# usb-board.net
KiCad netlist of a schematic drawn in EAGLE
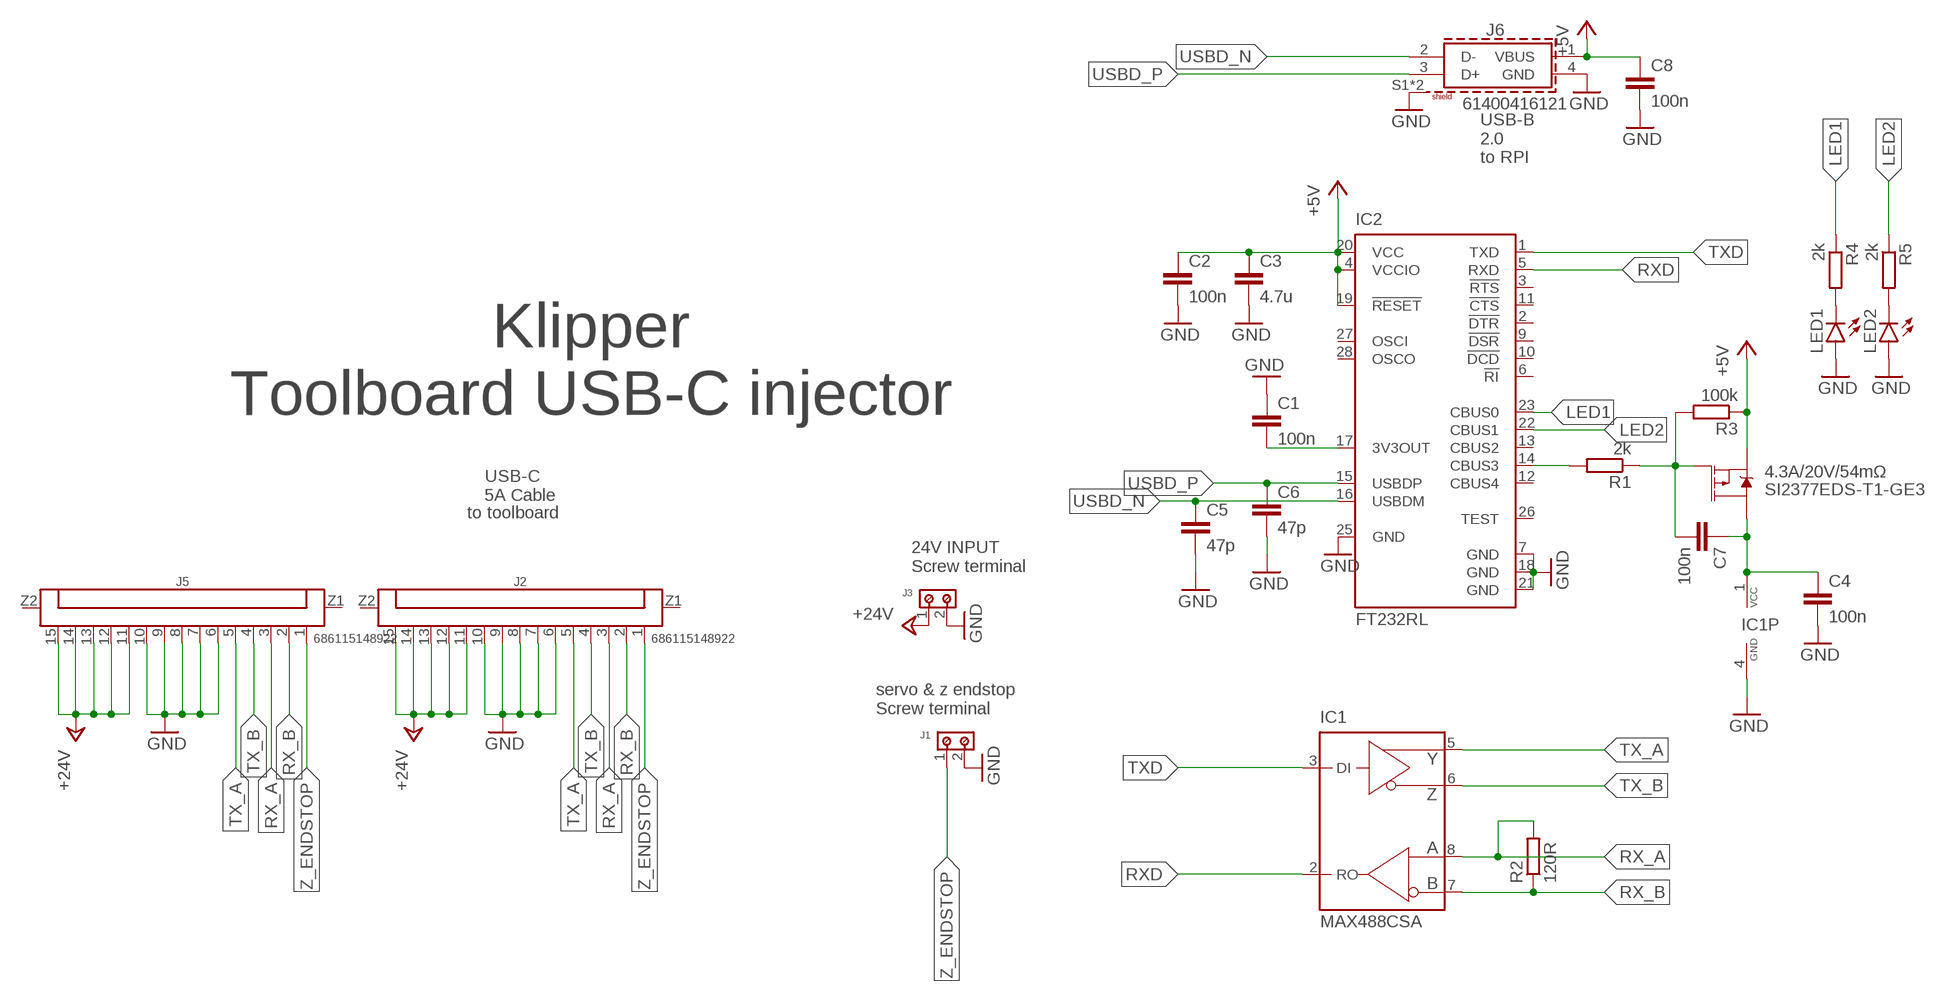
[diagram p0: schematic, sheet 1]

(export (version "E")
  (design (tool "Eeschema 10.0.6"))
  (components
    (comp (ref "C1")
      (value "100n")
      (footprint "eagle-import:C0805")
      (libsource (lib "eagle-import") (part "C-EUC0805"))
    )
    (comp (ref "C2")
      (value "100n")
      (footprint "eagle-import:C0805")
      (libsource (lib "eagle-import") (part "C-EUC0805"))
    )
    (comp (ref "C3")
      (value "4.7u")
      (footprint "eagle-import:C0805")
      (libsource (lib "eagle-import") (part "C-EUC0805"))
    )
    (comp (ref "C4")
      (value "100n")
      (footprint "eagle-import:C0805")
      (libsource (lib "eagle-import") (part "C-EUC0805"))
    )
    (comp (ref "C5")
      (value "47p")
      (footprint "eagle-import:C0805")
      (libsource (lib "eagle-import") (part "C-EUC0805"))
    )
    (comp (ref "C6")
      (value "47p")
      (footprint "eagle-import:C0805")
      (libsource (lib "eagle-import") (part "C-EUC0805"))
    )
    (comp (ref "C7")
      (value "100n")
      (footprint "eagle-import:C0805")
      (libsource (lib "eagle-import") (part "C-EUC0805"))
    )
    (comp (ref "C8")
      (value "100n")
      (footprint "eagle-import:C0805")
      (libsource (lib "eagle-import") (part "C-EUC0805"))
    )
    (comp (ref "IC1")
      (value "MAX488CSA")
      (footprint "eagle-import:SO08")
      (fields (field (name "MF") "MAXIM"))
      (libsource (lib "eagle-import") (part "MAX488CSA"))
    )
    (comp (ref "IC2")
      (value "FT232RL")
      (footprint "eagle-import:SSOP28")
      (libsource (lib "eagle-import") (part "FT232RL"))
    )
    (comp (ref "J1")
      (value "691103110002")
      (footprint "eagle-import:691103110002")
      (libsource (lib "eagle-import") (part "691103110002"))
    )
    (comp (ref "J2")
      (value "686115148922")
      (footprint "eagle-import:686115148922")
      (libsource (lib "eagle-import") (part "6861XX148922_686115148922"))
    )
    (comp (ref "J3")
      (value "691103110002")
      (footprint "eagle-import:691103110002")
      (libsource (lib "eagle-import") (part "691103110002"))
    )
    (comp (ref "J5")
      (value "686115148922")
      (footprint "eagle-import:686115148922")
      (libsource (lib "eagle-import") (part "6861XX148922_686115148922"))
    )
    (comp (ref "J6")
      (value "61400416121")
      (footprint "eagle-import:61400416121")
      (libsource (lib "eagle-import") (part "61400416121"))
    )
    (comp (ref "LED1")
      (value "LEDCHIPLED_0805")
      (footprint "eagle-import:CHIPLED_0805")
      (libsource (lib "eagle-import") (part "LEDCHIPLED_0805"))
    )
    (comp (ref "LED2")
      (value "LEDCHIPLED_0805")
      (footprint "eagle-import:CHIPLED_0805")
      (libsource (lib "eagle-import") (part "LEDCHIPLED_0805"))
    )
    (comp (ref "R1")
      (value "2k")
      (footprint "eagle-import:R0805")
      (libsource (lib "eagle-import") (part "R-EU_R0805"))
    )
    (comp (ref "R2")
      (value "120R")
      (footprint "eagle-import:R0805")
      (libsource (lib "eagle-import") (part "R-EU_R0805"))
    )
    (comp (ref "R3")
      (value "100k")
      (footprint "eagle-import:R0805")
      (libsource (lib "eagle-import") (part "R-EU_R0805"))
    )
    (comp (ref "R4")
      (value "2k")
      (footprint "eagle-import:R0805")
      (libsource (lib "eagle-import") (part "R-EU_R0805"))
    )
    (comp (ref "R5")
      (value "2k")
      (footprint "eagle-import:R0805")
      (libsource (lib "eagle-import") (part "R-EU_R0805"))
    )
    (comp (ref "SI2377EDS-T1-GE3")
      (value "4.3A/20V/54mΩ")
      (footprint "eagle-import:SOT23-3")
      (libsource (lib "eagle-import") (part "MOSFET_PCH-IRLML2244"))
    )
  )
  (nets
    (net (code "1") (name "+5V") (class "Default")
      (node (ref "C2") (pin "1") (pinfunction "1_1") (pintype "passive"))
      (node (ref "C3") (pin "1") (pinfunction "1_1") (pintype "passive"))
      (node (ref "C8") (pin "1") (pinfunction "1_1") (pintype "passive"))
      (node (ref "IC2") (pin "19") (pinfunction "~{RESET}_19") (pintype "input"))
      (node (ref "IC2") (pin "20") (pinfunction "VCC_20") (pintype "power_in"))
      (node (ref "IC2") (pin "4") (pinfunction "VCCIO_4") (pintype "power_in"))
      (node (ref "J6") (pin "1") (pinfunction "VBUS_1") (pintype "passive"))
      (node (ref "R3") (pin "1") (pinfunction "1_1") (pintype "passive"))
      (node (ref "SI2377EDS-T1-GE3") (pin "2") (pinfunction "S_2") (pintype "bidirectional"))
    )
    (net (code "2") (name "+24V") (class "Default")
      (node (ref "J2") (pin "11") (pinfunction "11_11") (pintype "passive"))
      (node (ref "J2") (pin "12") (pinfunction "12_12") (pintype "passive"))
      (node (ref "J2") (pin "13") (pinfunction "13_13") (pintype "passive"))
      (node (ref "J2") (pin "14") (pinfunction "14_14") (pintype "passive"))
      (node (ref "J2") (pin "15") (pinfunction "15_15") (pintype "passive"))
      (node (ref "J3") (pin "1") (pinfunction "1_1") (pintype "passive"))
      (node (ref "J5") (pin "11") (pinfunction "11_11") (pintype "passive"))
      (node (ref "J5") (pin "12") (pinfunction "12_12") (pintype "passive"))
      (node (ref "J5") (pin "13") (pinfunction "13_13") (pintype "passive"))
      (node (ref "J5") (pin "14") (pinfunction "14_14") (pintype "passive"))
      (node (ref "J5") (pin "15") (pinfunction "15_15") (pintype "passive"))
    )
    (net (code "3") (name "GND") (class "Default")
      (node (ref "C1") (pin "1") (pinfunction "1_1") (pintype "passive"))
      (node (ref "C2") (pin "2") (pinfunction "2_2") (pintype "passive"))
      (node (ref "C3") (pin "2") (pinfunction "2_2") (pintype "passive"))
      (node (ref "C4") (pin "2") (pinfunction "2_2") (pintype "passive"))
      (node (ref "C5") (pin "2") (pinfunction "2_2") (pintype "passive"))
      (node (ref "C6") (pin "2") (pinfunction "2_2") (pintype "passive"))
      (node (ref "C8") (pin "2") (pinfunction "2_2") (pintype "passive"))
      (node (ref "IC1") (pin "4") (pinfunction "GND_4") (pintype "power_in"))
      (node (ref "IC2") (pin "18") (pinfunction "GND_18") (pintype "power_in"))
      (node (ref "IC2") (pin "21") (pinfunction "GND_21") (pintype "power_in"))
      (node (ref "IC2") (pin "25") (pinfunction "GND_25") (pintype "power_in"))
      (node (ref "IC2") (pin "7") (pinfunction "GND_7") (pintype "power_in"))
      (node (ref "J1") (pin "2") (pinfunction "2_2") (pintype "passive"))
      (node (ref "J2") (pin "10") (pinfunction "10_10") (pintype "passive"))
      (node (ref "J2") (pin "6") (pinfunction "6_6") (pintype "passive"))
      (node (ref "J2") (pin "7") (pinfunction "7_7") (pintype "passive"))
      (node (ref "J2") (pin "8") (pinfunction "8_8") (pintype "passive"))
      (node (ref "J2") (pin "9") (pinfunction "9_9") (pintype "passive"))
      (node (ref "J3") (pin "2") (pinfunction "2_2") (pintype "passive"))
      (node (ref "J5") (pin "10") (pinfunction "10_10") (pintype "passive"))
      (node (ref "J5") (pin "6") (pinfunction "6_6") (pintype "passive"))
      (node (ref "J5") (pin "7") (pinfunction "7_7") (pintype "passive"))
      (node (ref "J5") (pin "8") (pinfunction "8_8") (pintype "passive"))
      (node (ref "J5") (pin "9") (pinfunction "9_9") (pintype "passive"))
      (node (ref "J6") (pin "4") (pinfunction "GND_4") (pintype "passive"))
      (node (ref "J6") (pin "S1") (pinfunction "SHIELD_S1") (pintype "passive"))
      (node (ref "J6") (pin "S2") (pinfunction "SHIELD_S2") (pintype "passive"))
      (node (ref "LED1") (pin "A") (pinfunction "A_A") (pintype "passive"))
      (node (ref "LED2") (pin "A") (pinfunction "A_A") (pintype "passive"))
    )
    (net (code "4") (name "LED1") (class "Default")
      (node (ref "IC2") (pin "23") (pinfunction "CBUS0_23") (pintype "bidirectional"))
      (node (ref "R4") (pin "1") (pinfunction "1_1") (pintype "passive"))
    )
    (net (code "5") (name "LED2") (class "Default")
      (node (ref "IC2") (pin "22") (pinfunction "CBUS1_22") (pintype "bidirectional"))
      (node (ref "R5") (pin "1") (pinfunction "1_1") (pintype "passive"))
    )
    (net (code "6") (name "Net-(IC1B-VCC)") (class "Default")
      (node (ref "C4") (pin "1") (pinfunction "1_1") (pintype "passive"))
      (node (ref "C7") (pin "1") (pinfunction "1_1") (pintype "passive"))
      (node (ref "IC1") (pin "1") (pinfunction "VCC_1") (pintype "power_in"))
      (node (ref "SI2377EDS-T1-GE3") (pin "3") (pinfunction "D_3") (pintype "bidirectional"))
    )
    (net (code "7") (name "Net-(IC2-3V3OUT)") (class "Default")
      (node (ref "C1") (pin "2") (pinfunction "2_2") (pintype "passive"))
      (node (ref "IC2") (pin "17") (pinfunction "3V3OUT_17") (pintype "output"))
    )
    (net (code "8") (name "Net-(IC2-CBUS3)") (class "Default")
      (node (ref "IC2") (pin "14") (pinfunction "CBUS3_14") (pintype "bidirectional"))
      (node (ref "R1") (pin "2") (pinfunction "2_2") (pintype "passive"))
    )
    (net (code "9") (name "Net-(LED1-PadC)") (class "Default")
      (node (ref "LED1") (pin "C") (pinfunction "C_C") (pintype "passive"))
      (node (ref "R4") (pin "2") (pinfunction "2_2") (pintype "passive"))
    )
    (net (code "10") (name "Net-(LED2-PadC)") (class "Default")
      (node (ref "LED2") (pin "C") (pinfunction "C_C") (pintype "passive"))
      (node (ref "R5") (pin "2") (pinfunction "2_2") (pintype "passive"))
    )
    (net (code "11") (name "Net-(SI2377EDS-T1-GE3-G)") (class "Default")
      (node (ref "C7") (pin "2") (pinfunction "2_2") (pintype "passive"))
      (node (ref "R1") (pin "1") (pinfunction "1_1") (pintype "passive"))
      (node (ref "R3") (pin "2") (pinfunction "2_2") (pintype "passive"))
      (node (ref "SI2377EDS-T1-GE3") (pin "1") (pinfunction "G_1") (pintype "bidirectional"))
    )
    (net (code "12") (name "RXD") (class "Default")
      (node (ref "IC1") (pin "2") (pinfunction "RO_2") (pintype "output"))
      (node (ref "IC2") (pin "5") (pinfunction "RXD_5") (pintype "input"))
    )
    (net (code "13") (name "RX_A") (class "Default")
      (node (ref "IC1") (pin "8") (pinfunction "A_8") (pintype "input"))
      (node (ref "J2") (pin "3") (pinfunction "3_3") (pintype "passive"))
      (node (ref "J5") (pin "3") (pinfunction "3_3") (pintype "passive"))
      (node (ref "R2") (pin "2") (pinfunction "2_2") (pintype "passive"))
    )
    (net (code "14") (name "RX_B") (class "Default")
      (node (ref "IC1") (pin "7") (pinfunction "B_7") (pintype "input"))
      (node (ref "J2") (pin "2") (pinfunction "2_2") (pintype "passive"))
      (node (ref "J5") (pin "2") (pinfunction "2_2") (pintype "passive"))
      (node (ref "R2") (pin "1") (pinfunction "1_1") (pintype "passive"))
    )
    (net (code "15") (name "TXD") (class "Default")
      (node (ref "IC1") (pin "3") (pinfunction "DI_3") (pintype "input"))
      (node (ref "IC2") (pin "1") (pinfunction "TXD_1") (pintype "output"))
    )
    (net (code "16") (name "TX_A") (class "Default")
      (node (ref "IC1") (pin "5") (pinfunction "Y_5") (pintype "output"))
      (node (ref "J2") (pin "5") (pinfunction "5_5") (pintype "passive"))
      (node (ref "J5") (pin "5") (pinfunction "5_5") (pintype "passive"))
    )
    (net (code "17") (name "TX_B") (class "Default")
      (node (ref "IC1") (pin "6") (pinfunction "Z_6") (pintype "output"))
      (node (ref "J2") (pin "4") (pinfunction "4_4") (pintype "passive"))
      (node (ref "J5") (pin "4") (pinfunction "4_4") (pintype "passive"))
    )
    (net (code "18") (name "USBD_N") (class "Default")
      (node (ref "C5") (pin "1") (pinfunction "1_1") (pintype "passive"))
      (node (ref "IC2") (pin "16") (pinfunction "USBDM_16") (pintype "bidirectional"))
      (node (ref "J6") (pin "2") (pinfunction "D-_2") (pintype "passive"))
    )
    (net (code "19") (name "USBD_P") (class "Default")
      (node (ref "C6") (pin "1") (pinfunction "1_1") (pintype "passive"))
      (node (ref "IC2") (pin "15") (pinfunction "USBDP_15") (pintype "bidirectional"))
      (node (ref "J6") (pin "3") (pinfunction "D+_3") (pintype "passive"))
    )
    (net (code "20") (name "Z_ENDSTOP") (class "Default")
      (node (ref "J1") (pin "1") (pinfunction "1_1") (pintype "passive"))
      (node (ref "J2") (pin "1") (pinfunction "1_1") (pintype "passive"))
      (node (ref "J5") (pin "1") (pinfunction "1_1") (pintype "passive"))
    )
    (net (code "21") (name "unconnected-(IC2-CBUS2-Pad13)") (class "Default")
      (node (ref "IC2") (pin "13") (pinfunction "CBUS2_13") (pintype "bidirectional"))
    )
    (net (code "22") (name "unconnected-(IC2-CBUS4-Pad12)") (class "Default")
      (node (ref "IC2") (pin "12") (pinfunction "CBUS4_12") (pintype "bidirectional"))
    )
    (net (code "23") (name "unconnected-(IC2-OSCI-Pad27)") (class "Default")
      (node (ref "IC2") (pin "27") (pinfunction "OSCI_27") (pintype "input"))
    )
    (net (code "24") (name "unconnected-(IC2-OSCO-Pad28)") (class "Default")
      (node (ref "IC2") (pin "28") (pinfunction "OSCO_28") (pintype "output"))
    )
    (net (code "25") (name "unconnected-(IC2-TEST-Pad26)") (class "Default")
      (node (ref "IC2") (pin "26") (pinfunction "TEST_26") (pintype "input"))
    )
    (net (code "26") (name "unconnected-(IC2-~{CTS}-Pad11)") (class "Default")
      (node (ref "IC2") (pin "11") (pinfunction "~{CTS}_11") (pintype "input"))
    )
    (net (code "27") (name "unconnected-(IC2-~{DCD}-Pad10)") (class "Default")
      (node (ref "IC2") (pin "10") (pinfunction "~{DCD}_10") (pintype "input"))
    )
    (net (code "28") (name "unconnected-(IC2-~{DSR}-Pad9)") (class "Default")
      (node (ref "IC2") (pin "9") (pinfunction "~{DSR}_9") (pintype "input"))
    )
    (net (code "29") (name "unconnected-(IC2-~{DTR}-Pad2)") (class "Default")
      (node (ref "IC2") (pin "2") (pinfunction "~{DTR}_2") (pintype "output"))
    )
    (net (code "30") (name "unconnected-(IC2-~{RI}-Pad6)") (class "Default")
      (node (ref "IC2") (pin "6") (pinfunction "~{RI}_6") (pintype "input"))
    )
    (net (code "31") (name "unconnected-(IC2-~{RTS}-Pad3)") (class "Default")
      (node (ref "IC2") (pin "3") (pinfunction "~{RTS}_3") (pintype "output"))
    )
    (net (code "32") (name "unconnected-(J2-PadZ1)") (class "Default")
      (node (ref "J2") (pin "Z1") (pinfunction "Z1_Z1") (pintype "passive"))
    )
    (net (code "33") (name "unconnected-(J2-PadZ2)") (class "Default")
      (node (ref "J2") (pin "Z2") (pinfunction "Z2_Z2") (pintype "passive"))
    )
    (net (code "34") (name "unconnected-(J5-PadZ1)") (class "Default")
      (node (ref "J5") (pin "Z1") (pinfunction "Z1_Z1") (pintype "passive"))
    )
    (net (code "35") (name "unconnected-(J5-PadZ2)") (class "Default")
      (node (ref "J5") (pin "Z2") (pinfunction "Z2_Z2") (pintype "passive"))
    )
  )
)
